# Adorkable_Base_V2_EXP.net
KiCad netlist of a schematic drawn in EasyEDA Pro
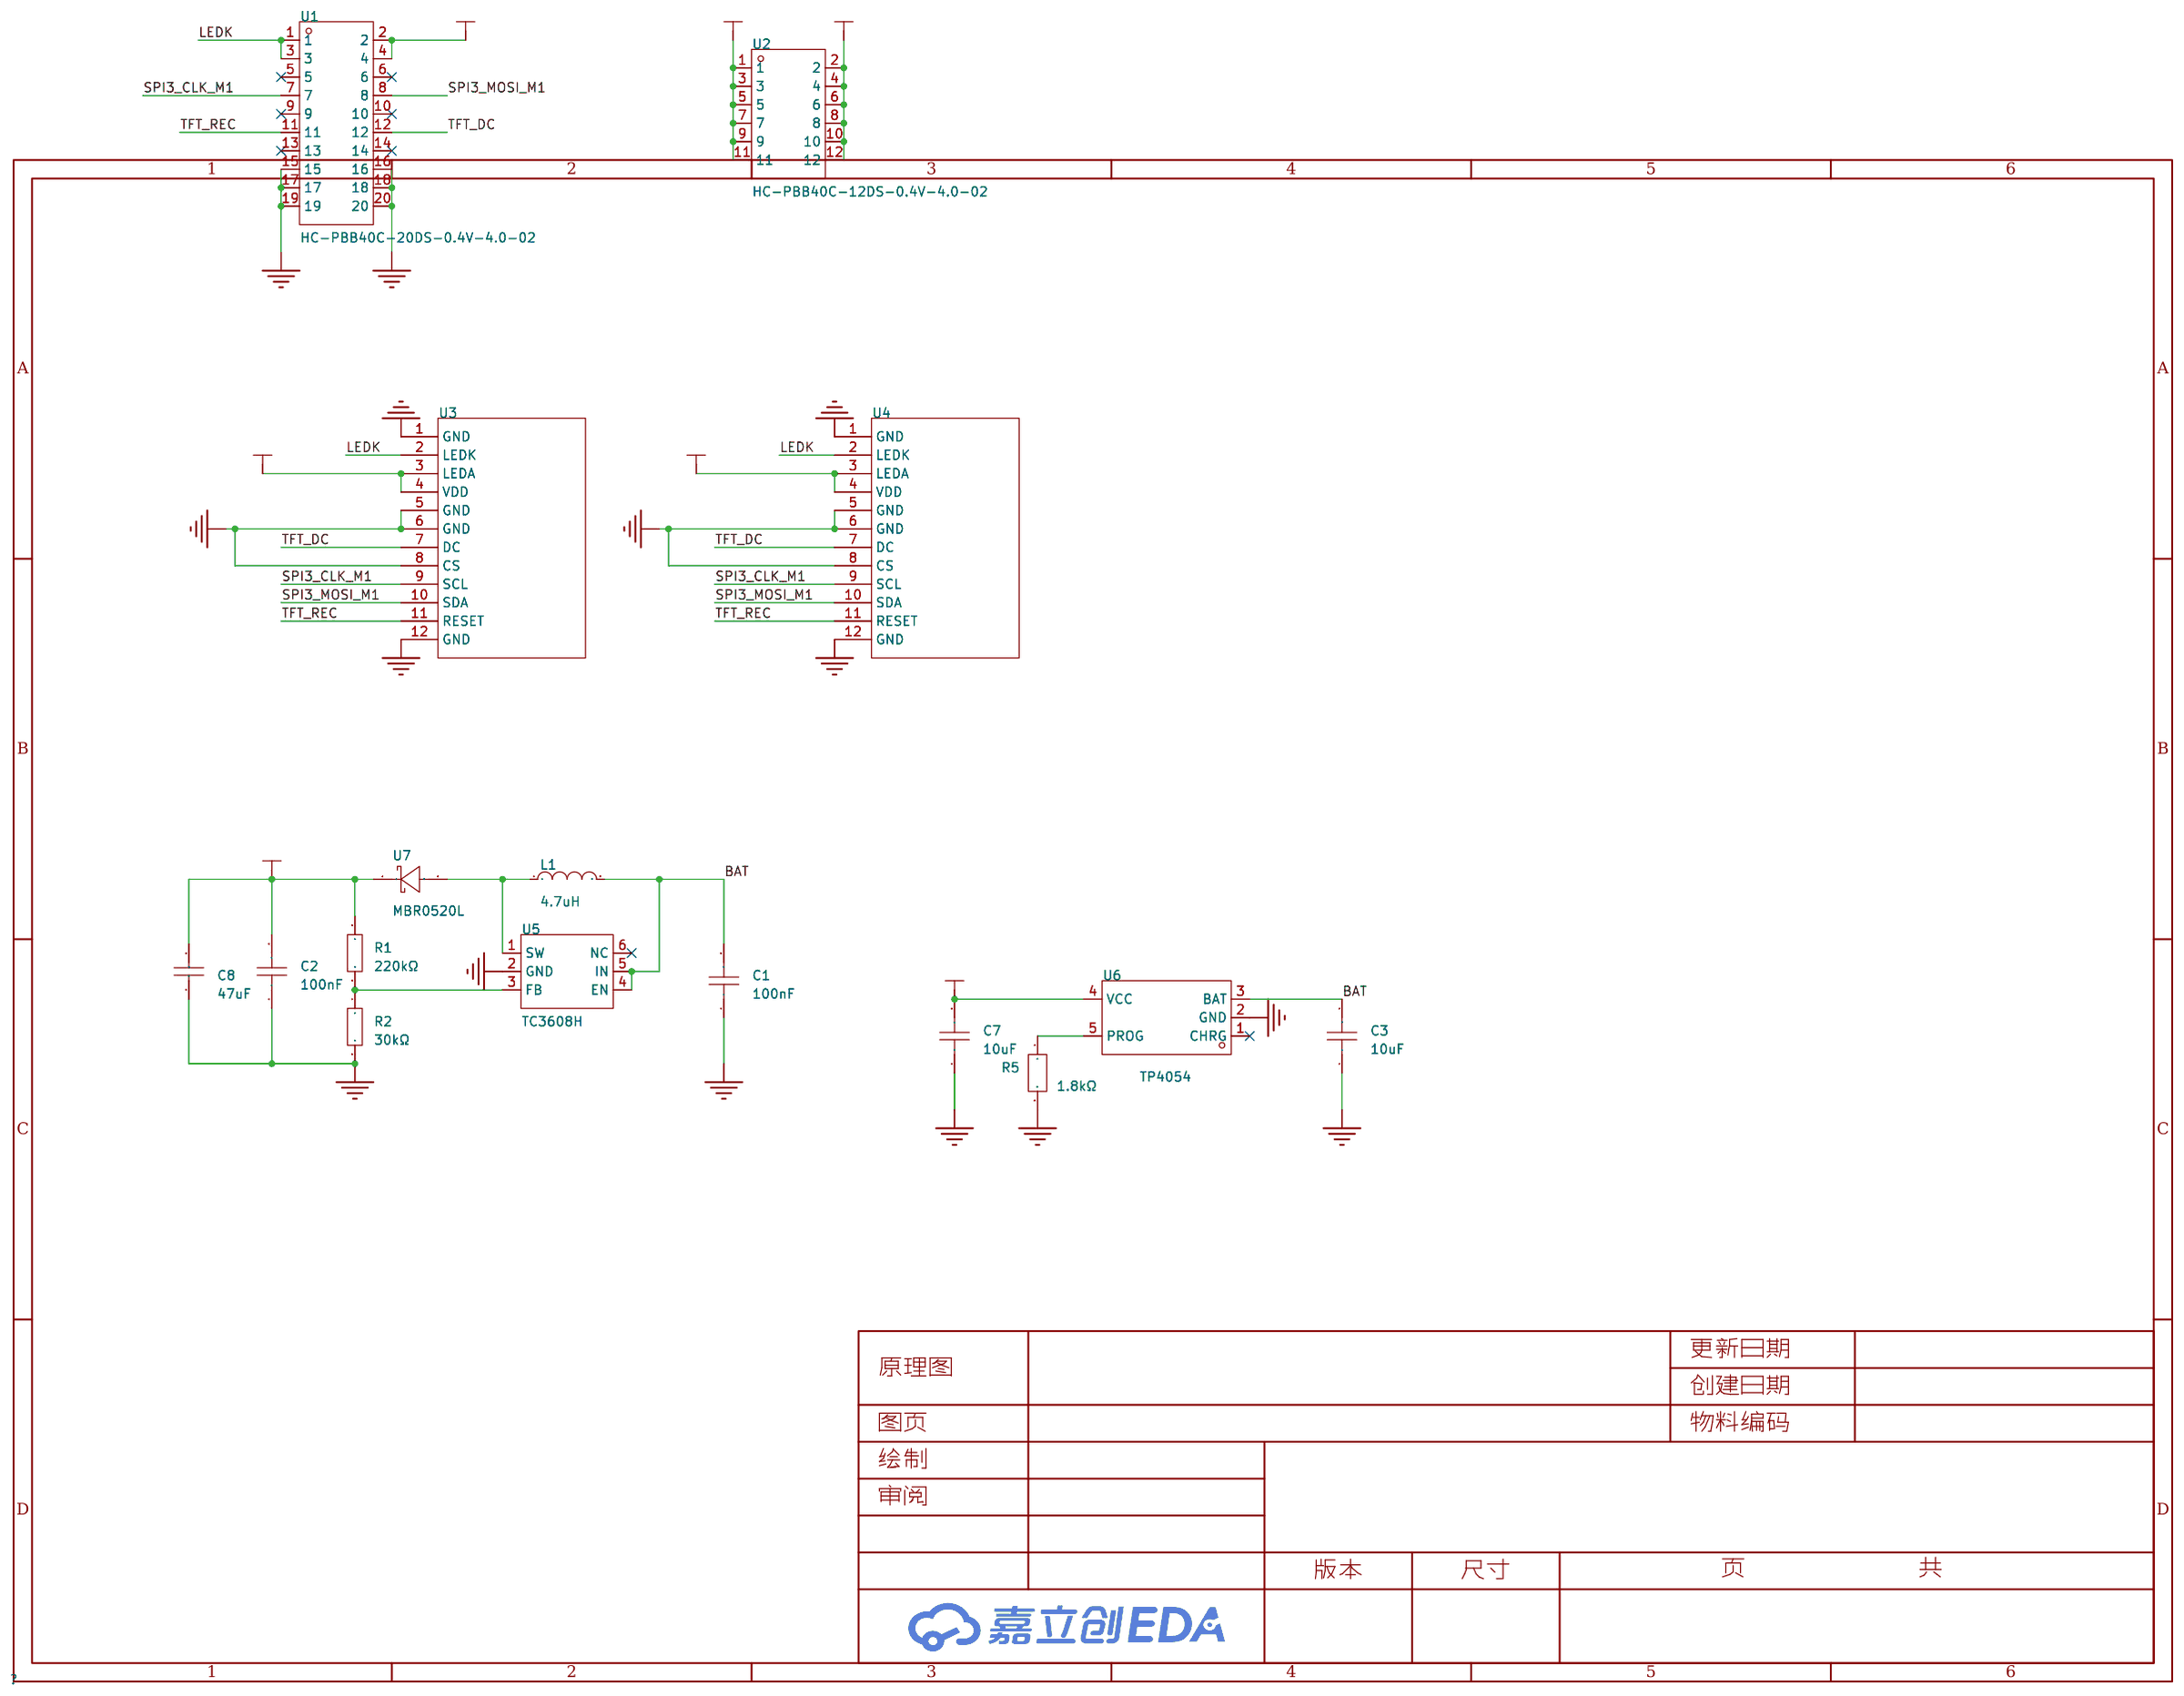
[diagram p0: schematic sheet]

(export (version "E")
  (design (tool "Eeschema 10.0.6"))
  (components
    (comp (ref "C1")
      (value "100nF")
      (footprint "easyedapro:C0603")
      (description "容值:100nF;精度:±10%;额定电压:50V;温度系数:X7R;")
      (fields
        (field (name "Manufacturer Part") "CL10B104KB8NNNC")
        (field (name "Manufacturer") "SAMSUNG(三星)")
      )
      (libsource (lib "easyedapro") (part "CL10B104KB8NNNC"))
    )
    (comp (ref "C2")
      (value "100nF")
      (footprint "easyedapro:C0603")
      (description "容值:100nF;精度:±10%;额定电压:50V;温度系数:X7R;")
      (fields
        (field (name "Manufacturer Part") "CL10B104KB8NNNC")
        (field (name "Manufacturer") "SAMSUNG(三星)")
      )
      (libsource (lib "easyedapro") (part "CL10B104KB8NNNC"))
    )
    (comp (ref "C3")
      (value "10uF")
      (footprint "easyedapro:C0603")
      (description "容值:10uF;精度:±10%;额定电压:10V;温度系数:X5R;")
      (fields
        (field (name "Manufacturer Part") "CL10A106KP8NNNC")
        (field (name "Manufacturer") "SAMSUNG(三星)")
      )
      (libsource (lib "easyedapro") (part "CL10A106KP8NNNC"))
    )
    (comp (ref "C7")
      (value "10uF")
      (footprint "easyedapro:C0603")
      (description "容值:10uF;精度:±10%;额定电压:10V;温度系数:X5R;")
      (fields
        (field (name "Manufacturer Part") "CL10A106KP8NNNC")
        (field (name "Manufacturer") "SAMSUNG(三星)")
      )
      (libsource (lib "easyedapro") (part "CL10A106KP8NNNC"))
    )
    (comp (ref "C8")
      (value "47uF")
      (footprint "easyedapro:C0603")
      (description "容值:47uF;精度:±20%;额定电压:6.3V;材质(温度系数):X5R;")
      (fields
        (field (name "Manufacturer Part") "GRM188R60J476ME15D")
        (field (name "Manufacturer") "muRata(村田)")
      )
      (libsource (lib "easyedapro") (part "GRM188R60J476ME15D"))
    )
    (comp (ref "L1")
      (value "4.7uH")
      (footprint "easyedapro:IND-SMD_L2.5-W2.0-VLS252012CX-150M")
      (description "电感值:4.7uH;精度:±20%;额定电流:2A;饱和电流(Isat):2.6A;类型:一体成型电感;")
      (fields
        (field (name "Manufacturer Part") "FTC252010S4R7MBCA")
        (field (name "Manufacturer") "cjiang(长江微电)")
      )
      (libsource (lib "easyedapro") (part "FTC252010S4R7MBCA"))
    )
    (comp (ref "R1")
      (value "220kΩ")
      (footprint "easyedapro:R0603")
      (description "电阻类型:厚膜电阻;阻值:220kΩ;精度:±1%;功率:100mW;工作电压:75V;温度系数:±100ppm/°C;")
      (fields
        (field (name "Manufacturer Part") "0603WAF2203T5E")
        (field (name "Manufacturer") "UNI-ROYAL(厚声)")
      )
      (libsource (lib "easyedapro") (part "0603WAF2203T5E"))
    )
    (comp (ref "R2")
      (value "30kΩ")
      (footprint "easyedapro:R0603")
      (description "电阻类型:厚膜电阻;阻值:30kΩ;精度:±1%;功率:100mW;工作电压:75V;温度系数:±100ppm/°C;")
      (fields
        (field (name "Manufacturer Part") "0603WAF3002T5E")
        (field (name "Manufacturer") "UNI-ROYAL(厚声)")
      )
      (libsource (lib "easyedapro") (part "0603WAF3002T5E"))
    )
    (comp (ref "R5")
      (value "1.8kΩ")
      (footprint "easyedapro:R0603")
      (description "电阻类型:厚膜电阻;阻值:1.8kΩ;精度:±1%;功率:100mW;工作电压:75V;温度系数:±100ppm/°C;")
      (fields (field (name "Manufacturer Part") "FRC0603F1801TS") (field (name "Manufacturer") "FOJAN(富捷)"))
      (libsource (lib "easyedapro") (part "FRC0603F1801TS"))
    )
    (comp (ref "U1")
      (value "HC-PBB40C-20DS-0.4V-4.0-02")
      (footprint "easyedapro:CONN-SMD_20P-P0.40_DF40C-20DS-0.4V")
      (description "PIN总数:20P;间距:0.4mm;安装方式:立贴;排数:2;额定电流:300mA;工作温度:-40°C~+85°C;")
      (fields (field (name "Manufacturer") "HCTL(华灿天禄)"))
      (libsource (lib "easyedapro") (part "HC-PBB40C-20DS-0.4V-4.0-02"))
    )
    (comp (ref "U2")
      (value "HC-PBB40C-12DS-0.4V-4.0-02")
      (footprint "easyedapro:CONN-SMD_12P-P0.40_HC-PBB40C-12DS-0.4V")
      (description "PIN总数:12P;间距:0.4mm;安装方式:立贴;排数:2;额定电流:300mA;工作温度:-40°C~+85°C;")
      (fields (field (name "Manufacturer") "HCTL(华灿天禄)"))
      (libsource (lib "easyedapro") (part "HC-PBB40C-12DS-0.4V-4.0-02"))
    )
    (comp (ref "U3") (value "~") (footprint "easyedapro:LCD") (libsource (lib "easyedapro") (part "LCD")))
    (comp (ref "U4") (value "~") (footprint "easyedapro:LCD") (libsource (lib "easyedapro") (part "LCD")))
    (comp (ref "U5")
      (value "TC3608H")
      (footprint "easyedapro:SOT-23-6_L2.9-W1.6-P0.95-LS2.8-BR")
      (description "功能类型:升压型;输出类型:-;工作电压:2.3V~15V;输出电压:-;输出电流:-;")
      (fields (field (name "Manufacturer") "FM(富满)"))
      (libsource (lib "easyedapro") (part "TC3608H."))
    )
    (comp (ref "U6")
      (value "TP4054")
      (footprint "easyedapro:TSOT-23-5_L2.9-W1.6-P0.95-LS2.8-BR")
      (description "电源电压:6.5V;最大充电电流:500mA;电池类型:锂离子/聚合物;电池节数:1;")
      (fields (field (name "Manufacturer") "UMW(友台半导体)"))
      (libsource (lib "easyedapro") (part "TP4054_C668215"))
    )
    (comp (ref "U7")
      (value "MBR0520L")
      (footprint "easyedapro:SOD-123_L2.7-W1.6-LS3.7-RD-1")
      (description "二极管配置:独立式;正向压降(Vf):385mV@500mA;直流反向耐压(Vr):20V;整流电流:500mA;")
      (fields (field (name "Manufacturer") "FUXINSEMI(富芯森美)"))
      (libsource (lib "easyedapro") (part "MBR0520L_C5563735"))
    )
  )
  (nets
    (net (code "1") (name "/BAT") (class "Default")
      (node (ref "C1") (pin "2") (pinfunction "2_2") (pintype "unspecified"))
      (node (ref "C3") (pin "2") (pinfunction "2_2") (pintype "unspecified"))
      (node (ref "L1") (pin "2") (pinfunction "2_2") (pintype "unspecified"))
      (node (ref "U5") (pin "4") (pinfunction "EN_4") (pintype "unspecified"))
      (node (ref "U5") (pin "5") (pinfunction "IN_5") (pintype "unspecified"))
      (node (ref "U6") (pin "3") (pinfunction "BAT_3") (pintype "unspecified"))
    )
    (net (code "2") (name "/LEDK") (class "Default")
      (node (ref "U1") (pin "1") (pinfunction "1_1") (pintype "unspecified"))
      (node (ref "U1") (pin "3") (pinfunction "3_3") (pintype "unspecified"))
      (node (ref "U3") (pin "2") (pinfunction "LEDK_2") (pintype "input"))
      (node (ref "U4") (pin "2") (pinfunction "LEDK_2") (pintype "input"))
    )
    (net (code "3") (name "/SPI3_CLK_M1") (class "Default")
      (node (ref "U1") (pin "7") (pinfunction "7_7") (pintype "unspecified"))
      (node (ref "U3") (pin "9") (pinfunction "SCL_9") (pintype "input"))
      (node (ref "U4") (pin "9") (pinfunction "SCL_9") (pintype "input"))
    )
    (net (code "4") (name "/SPI3_MOSI_M1") (class "Default")
      (node (ref "U1") (pin "8") (pinfunction "8_8") (pintype "unspecified"))
      (node (ref "U3") (pin "10") (pinfunction "SDA_10") (pintype "input"))
      (node (ref "U4") (pin "10") (pinfunction "SDA_10") (pintype "input"))
    )
    (net (code "5") (name "/TFT_DC") (class "Default")
      (node (ref "U1") (pin "12") (pinfunction "12_12") (pintype "unspecified"))
      (node (ref "U3") (pin "7") (pinfunction "DC_7") (pintype "input"))
      (node (ref "U4") (pin "7") (pinfunction "DC_7") (pintype "input"))
    )
    (net (code "6") (name "/TFT_REC") (class "Default")
      (node (ref "U1") (pin "11") (pinfunction "11_11") (pintype "unspecified"))
      (node (ref "U3") (pin "11") (pinfunction "RESET_11") (pintype "input"))
      (node (ref "U4") (pin "11") (pinfunction "RESET_11") (pintype "input"))
    )
    (net (code "7") (name "GND") (class "Default")
      (node (ref "C1") (pin "1") (pinfunction "1_1") (pintype "unspecified"))
      (node (ref "C2") (pin "1") (pinfunction "1_1") (pintype "unspecified"))
      (node (ref "C3") (pin "1") (pinfunction "1_1") (pintype "unspecified"))
      (node (ref "C7") (pin "1") (pinfunction "1_1") (pintype "unspecified"))
      (node (ref "C8") (pin "1") (pinfunction "1_1") (pintype "input"))
      (node (ref "R2") (pin "2") (pinfunction "2_2") (pintype "input"))
      (node (ref "R5") (pin "2") (pinfunction "2_2") (pintype "unspecified"))
      (node (ref "U1") (pin "15") (pinfunction "15_15") (pintype "unspecified"))
      (node (ref "U1") (pin "16") (pinfunction "16_16") (pintype "unspecified"))
      (node (ref "U1") (pin "17") (pinfunction "17_17") (pintype "unspecified"))
      (node (ref "U1") (pin "18") (pinfunction "18_18") (pintype "unspecified"))
      (node (ref "U1") (pin "19") (pinfunction "19_19") (pintype "unspecified"))
      (node (ref "U1") (pin "20") (pinfunction "20_20") (pintype "unspecified"))
      (node (ref "U3") (pin "1") (pinfunction "GND_1") (pintype "input"))
      (node (ref "U3") (pin "12") (pinfunction "GND_12") (pintype "input"))
      (node (ref "U3") (pin "5") (pinfunction "GND_5") (pintype "input"))
      (node (ref "U3") (pin "6") (pinfunction "GND_6") (pintype "input"))
      (node (ref "U3") (pin "8") (pinfunction "CS_8") (pintype "input"))
      (node (ref "U4") (pin "1") (pinfunction "GND_1") (pintype "input"))
      (node (ref "U4") (pin "12") (pinfunction "GND_12") (pintype "input"))
      (node (ref "U4") (pin "5") (pinfunction "GND_5") (pintype "input"))
      (node (ref "U4") (pin "6") (pinfunction "GND_6") (pintype "input"))
      (node (ref "U4") (pin "8") (pinfunction "CS_8") (pintype "input"))
      (node (ref "U5") (pin "2") (pinfunction "GND_2") (pintype "unspecified"))
      (node (ref "U6") (pin "2") (pinfunction "GND_2") (pintype "unspecified"))
    )
    (net (code "8") (name "Net-(U5-FB)") (class "Default")
      (node (ref "R1") (pin "2") (pinfunction "2_2") (pintype "input"))
      (node (ref "R2") (pin "1") (pinfunction "1_1") (pintype "input"))
      (node (ref "U5") (pin "3") (pinfunction "FB_3") (pintype "unspecified"))
    )
    (net (code "9") (name "Net-(U5-SW)") (class "Default")
      (node (ref "L1") (pin "1") (pinfunction "1_1") (pintype "unspecified"))
      (node (ref "U5") (pin "1") (pinfunction "SW_1") (pintype "unspecified"))
      (node (ref "U7") (pin "2") (pinfunction "2_2") (pintype "unspecified"))
    )
    (net (code "10") (name "Net-(U6-PROG)") (class "Default")
      (node (ref "R5") (pin "1") (pinfunction "1_1") (pintype "unspecified"))
      (node (ref "U6") (pin "5") (pinfunction "PROG_5") (pintype "unspecified"))
    )
    (net (code "11") (name "VCC_3V3") (class "Default")
      (node (ref "U1") (pin "2") (pinfunction "2_2") (pintype "unspecified"))
      (node (ref "U1") (pin "4") (pinfunction "4_4") (pintype "unspecified"))
      (node (ref "U3") (pin "3") (pinfunction "LEDA_3") (pintype "input"))
      (node (ref "U3") (pin "4") (pinfunction "VDD_4") (pintype "input"))
      (node (ref "U4") (pin "3") (pinfunction "LEDA_3") (pintype "input"))
      (node (ref "U4") (pin "4") (pinfunction "VDD_4") (pintype "input"))
    )
    (net (code "12") (name "VCC_5V") (class "Default")
      (node (ref "C7") (pin "2") (pinfunction "2_2") (pintype "unspecified"))
      (node (ref "U2") (pin "1") (pinfunction "1_1") (pintype "unspecified"))
      (node (ref "U2") (pin "11") (pinfunction "11_11") (pintype "unspecified"))
      (node (ref "U2") (pin "3") (pinfunction "3_3") (pintype "unspecified"))
      (node (ref "U2") (pin "5") (pinfunction "5_5") (pintype "unspecified"))
      (node (ref "U2") (pin "7") (pinfunction "7_7") (pintype "unspecified"))
      (node (ref "U2") (pin "9") (pinfunction "9_9") (pintype "unspecified"))
      (node (ref "U6") (pin "4") (pinfunction "VCC_4") (pintype "unspecified"))
    )
    (net (code "13") (name "VCC_OUT") (class "Default")
      (node (ref "C2") (pin "2") (pinfunction "2_2") (pintype "unspecified"))
      (node (ref "C8") (pin "2") (pinfunction "2_2") (pintype "input"))
      (node (ref "R1") (pin "1") (pinfunction "1_1") (pintype "input"))
      (node (ref "U2") (pin "10") (pinfunction "10_10") (pintype "unspecified"))
      (node (ref "U2") (pin "12") (pinfunction "12_12") (pintype "unspecified"))
      (node (ref "U2") (pin "2") (pinfunction "2_2") (pintype "unspecified"))
      (node (ref "U2") (pin "4") (pinfunction "4_4") (pintype "unspecified"))
      (node (ref "U2") (pin "6") (pinfunction "6_6") (pintype "unspecified"))
      (node (ref "U2") (pin "8") (pinfunction "8_8") (pintype "unspecified"))
      (node (ref "U7") (pin "1") (pinfunction "1_1") (pintype "unspecified"))
    )
    (net (code "14") (name "unconnected-(U1-Pad5)") (class "Default")
      (node (ref "U1") (pin "5") (pinfunction "5_5") (pintype "unspecified+no_connect"))
    )
    (net (code "15") (name "unconnected-(U1-Pad6)") (class "Default")
      (node (ref "U1") (pin "6") (pinfunction "6_6") (pintype "unspecified+no_connect"))
    )
    (net (code "16") (name "unconnected-(U1-Pad9)") (class "Default")
      (node (ref "U1") (pin "9") (pinfunction "9_9") (pintype "unspecified+no_connect"))
    )
    (net (code "17") (name "unconnected-(U1-Pad10)") (class "Default")
      (node (ref "U1") (pin "10") (pinfunction "10_10") (pintype "unspecified+no_connect"))
    )
    (net (code "18") (name "unconnected-(U1-Pad13)") (class "Default")
      (node (ref "U1") (pin "13") (pinfunction "13_13") (pintype "unspecified+no_connect"))
    )
    (net (code "19") (name "unconnected-(U1-Pad14)") (class "Default")
      (node (ref "U1") (pin "14") (pinfunction "14_14") (pintype "unspecified+no_connect"))
    )
    (net (code "20") (name "unconnected-(U5-NC-Pad6)") (class "Default")
      (node (ref "U5") (pin "6") (pinfunction "NC_6") (pintype "unspecified+no_connect"))
    )
    (net (code "21") (name "unconnected-(U6-CHRG-Pad1)") (class "Default")
      (node (ref "U6") (pin "1") (pinfunction "CHRG_1") (pintype "unspecified+no_connect"))
    )
  )
)
